# openSX70_MEROE_V7-5_20190606-TSL237T.net
KiCad netlist of a schematic drawn in EAGLE
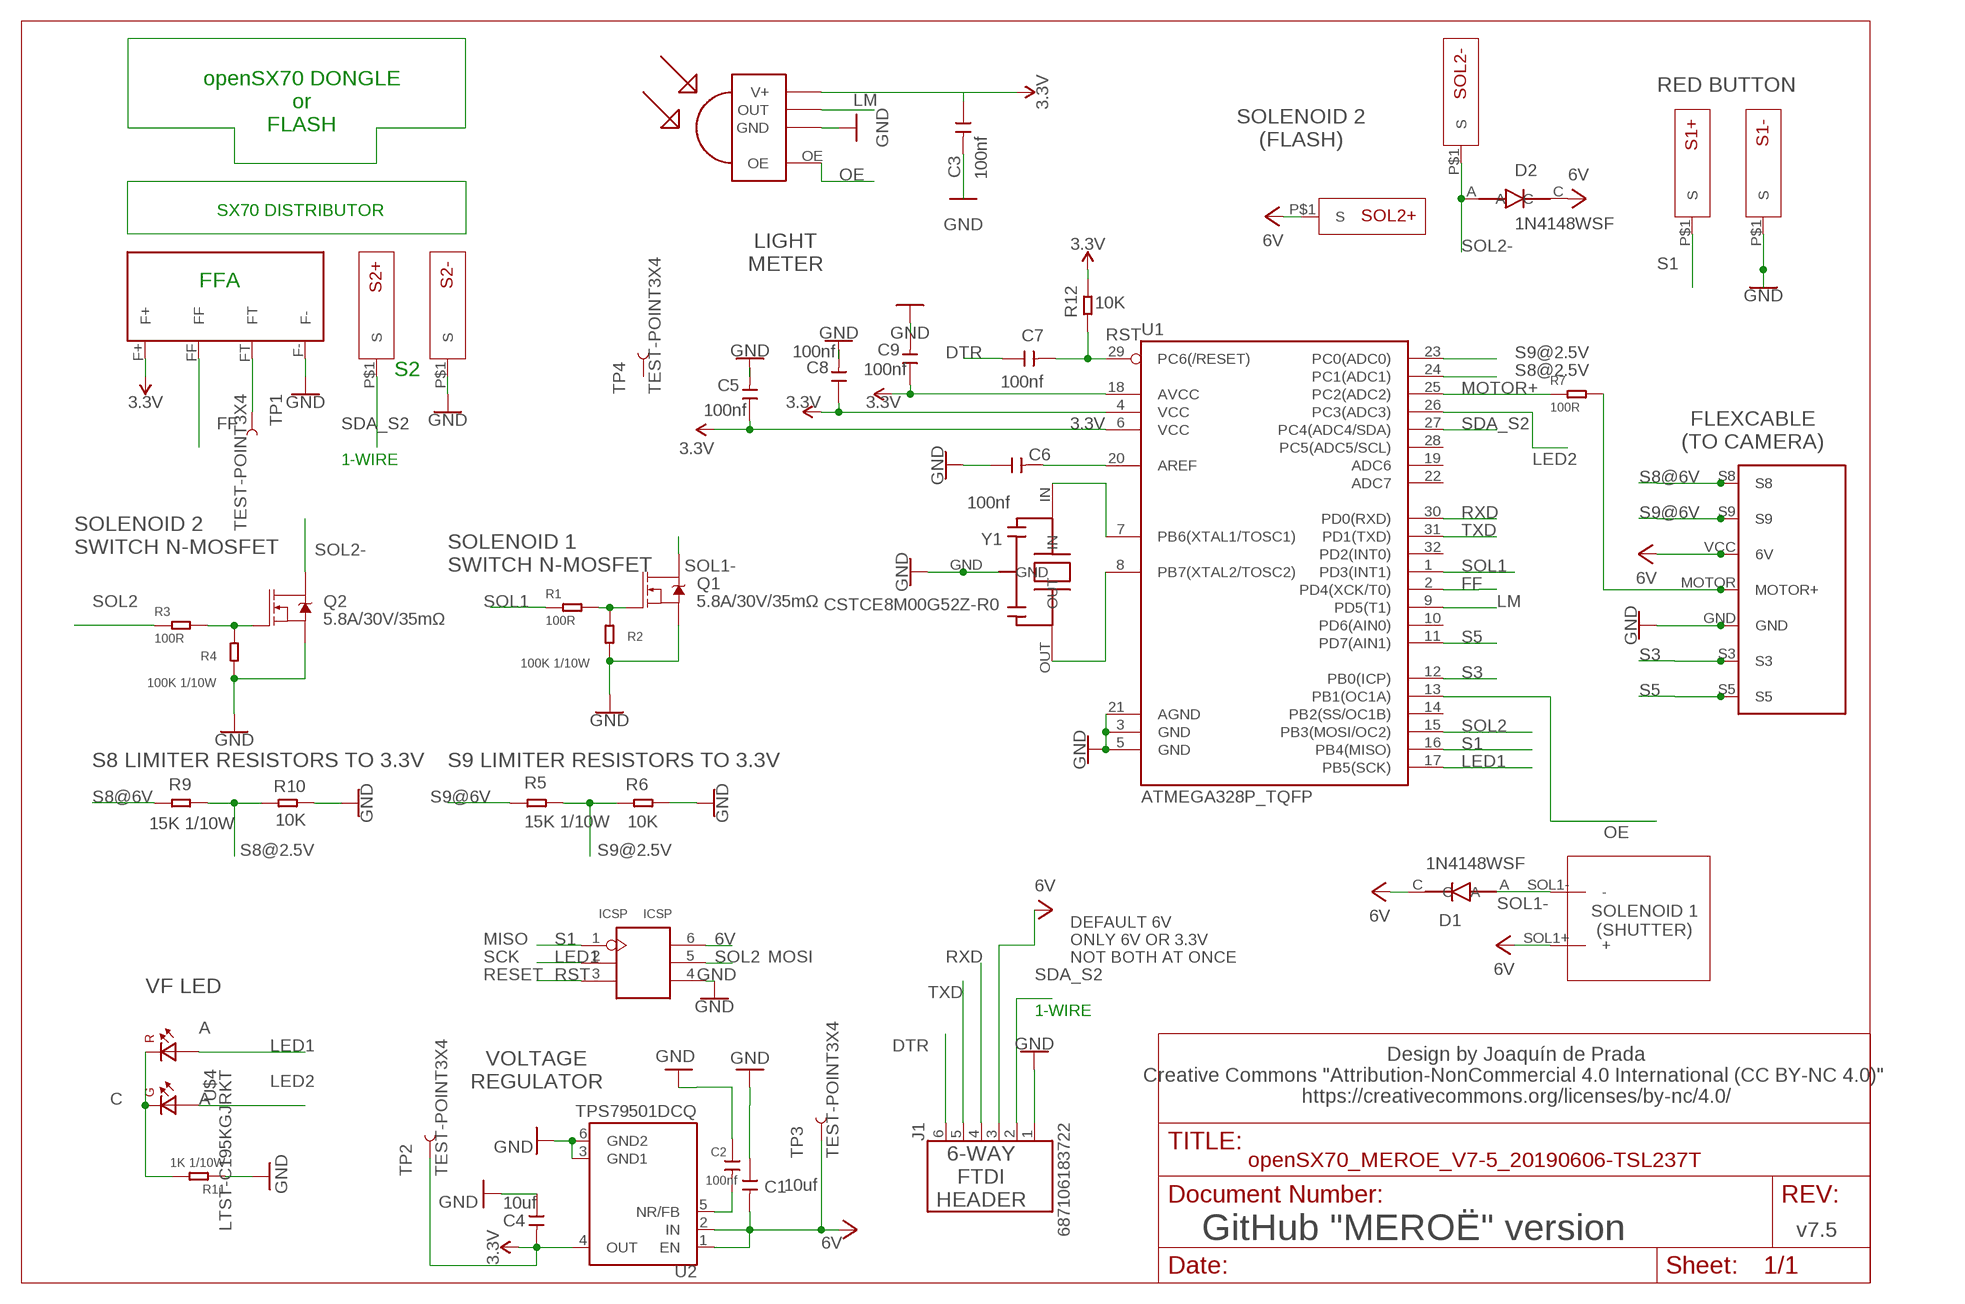
[diagram p0: schematic, sheet 1]

(export (version "E")
  (design (tool "Eeschema 10.0.6"))
  (components
    (comp (ref "C1")
      (value "10uf")
      (footprint "eagle-import:C0603")
      (fields (field (name "MPN") "CC0603KRX5R6BB106"))
      (libsource (lib "eagle-import") (part "CERAMIC-10UF-10V-10%-X5R(0603)"))
    )
    (comp (ref "C2")
      (value "100nf")
      (footprint "eagle-import:C0603")
      (fields (field (name "MPN") "CC0603KRX7R9BB104"))
      (libsource (lib "eagle-import") (part "CERAMIC-100NF-50V-10%-X7R(0603)"))
    )
    (comp (ref "C3")
      (value "100nf")
      (footprint "eagle-import:C0603")
      (fields (field (name "MPN") "CC0603KRX7R9BB104"))
      (libsource (lib "eagle-import") (part "CERAMIC-100NF-50V-10%-X7R(0603)"))
    )
    (comp (ref "C4")
      (value "10uf")
      (footprint "eagle-import:C0603")
      (fields (field (name "MPN") "CC0603KRX5R6BB106"))
      (libsource (lib "eagle-import") (part "CERAMIC-10UF-10V-10%-X5R(0603)"))
    )
    (comp (ref "C5")
      (value "100nf")
      (footprint "eagle-import:C0603")
      (fields (field (name "MPN") "CC0603KRX7R9BB104"))
      (libsource (lib "eagle-import") (part "CERAMIC-100NF-50V-10%-X7R(0603)"))
    )
    (comp (ref "C6")
      (value "100nf")
      (footprint "eagle-import:C0603")
      (fields (field (name "MPN") "CC0603KRX7R9BB104"))
      (libsource (lib "eagle-import") (part "CERAMIC-100NF-50V-10%-X7R(0603)"))
    )
    (comp (ref "C7")
      (value "100nf")
      (footprint "eagle-import:C0603")
      (fields (field (name "MPN") "CC0603KRX7R9BB104"))
      (libsource (lib "eagle-import") (part "CERAMIC-100NF-50V-10%-X7R(0603)"))
    )
    (comp (ref "C8")
      (value "100nf")
      (footprint "eagle-import:C0603")
      (fields (field (name "MPN") "CC0603KRX7R9BB104"))
      (libsource (lib "eagle-import") (part "CERAMIC-100NF-50V-10%-X7R(0603)"))
    )
    (comp (ref "C9")
      (value "100nf")
      (footprint "eagle-import:C0603")
      (fields (field (name "MPN") "CC0603KRX7R9BB104"))
      (libsource (lib "eagle-import") (part "CERAMIC-100NF-50V-10%-X7R(0603)"))
    )
    (comp (ref "D1")
      (value "1N4148WSF")
      (footprint "eagle-import:SODFL2512X100N")
      (fields (field (name "MANUFACTURER") "Fairchild Semiconductor"))
      (libsource (lib "eagle-import") (part "1N4148WS"))
    )
    (comp (ref "D2")
      (value "1N4148WSF")
      (footprint "eagle-import:SODFL2512X100N")
      (fields (field (name "MANUFACTURER") "Fairchild Semiconductor"))
      (libsource (lib "eagle-import") (part "1N4148WS"))
    )
    (comp (ref "ICSP")
      (value "ICSP")
      (footprint "eagle-import:H2X3-2.54")
      (libsource (lib "eagle-import") (part "ICSP"))
    )
    (comp (ref "J1")
      (value "687106183722")
      (footprint "eagle-import:687106183722")
      (fields (field (name "MF") "Wurth Electronics"))
      (libsource (lib "eagle-import") (part "687106183722"))
    )
    (comp (ref "Q1")
      (value "5.8A/30V/35mΩ")
      (footprint "eagle-import:SOT23-3")
      (libsource (lib "eagle-import") (part "MOSFET-NCH-AO3404A"))
    )
    (comp (ref "Q2")
      (value "5.8A/30V/35mΩ")
      (footprint "eagle-import:SOT23-3")
      (libsource (lib "eagle-import") (part "MOSFET-NCH-AO3404A"))
    )
    (comp (ref "R1")
      (value "100R")
      (footprint "eagle-import:R0603")
      (fields (field (name "MPN") "RC0603JR-07100RL"))
      (libsource (lib "eagle-import") (part "SMD-RES-100R-5%-1/10W(0603)"))
    )
    (comp (ref "R2")
      (value "100K 1/10W")
      (footprint "eagle-import:R0603")
      (fields (field (name "MPN") "RC0603JR-07100KL"))
      (libsource (lib "eagle-import") (part "SMD-RES-100K-5%-1/10W(0603)"))
    )
    (comp (ref "R3")
      (value "100R")
      (footprint "eagle-import:R0603")
      (fields (field (name "MPN") "RC0603JR-07100RL"))
      (libsource (lib "eagle-import") (part "SMD-RES-100R-5%-1/10W(0603)"))
    )
    (comp (ref "R4")
      (value "100K 1/10W")
      (footprint "eagle-import:R0603")
      (fields (field (name "MPN") "RC0603JR-07100KL"))
      (libsource (lib "eagle-import") (part "SMD-RES-100K-5%-1/10W(0603)"))
    )
    (comp (ref "R5")
      (value "15K 1/10W")
      (footprint "eagle-import:R0603")
      (fields (field (name "MPN") "RC0603FR-0715KL"))
      (libsource (lib "eagle-import") (part "SMD-RES-15K-1%-1/10W(0603)"))
    )
    (comp (ref "R6")
      (value "10K")
      (footprint "eagle-import:R0603")
      (fields (field (name "MPN") "RC0603FR-0710KL"))
      (libsource (lib "eagle-import") (part "SMD-RES-10K-1%-1/10W(0603)"))
    )
    (comp (ref "R7")
      (value "100R")
      (footprint "eagle-import:R0603")
      (fields (field (name "MPN") "RC0603JR-07100RL"))
      (libsource (lib "eagle-import") (part "SMD-RES-100R-5%-1/10W(0603)"))
    )
    (comp (ref "R9")
      (value "15K 1/10W")
      (footprint "eagle-import:R0603")
      (fields (field (name "MPN") "RC0603FR-0715KL"))
      (libsource (lib "eagle-import") (part "SMD-RES-15K-1%-1/10W(0603)"))
    )
    (comp (ref "R10")
      (value "10K")
      (footprint "eagle-import:R0603")
      (fields (field (name "MPN") "RC0603FR-0710KL"))
      (libsource (lib "eagle-import") (part "SMD-RES-10K-1%-1/10W(0603)"))
    )
    (comp (ref "R11")
      (value "1K 1/10W")
      (footprint "eagle-import:R0603")
      (fields (field (name "MPN") "RC0603JR-071KL"))
      (libsource (lib "eagle-import") (part "SMD-RES-1K-5%-1/10W(0603)"))
    )
    (comp (ref "R12")
      (value "10K")
      (footprint "eagle-import:R0603")
      (fields (field (name "MPN") "RC0603FR-0710KL"))
      (libsource (lib "eagle-import") (part "SMD-RES-10K-1%-1/10W(0603)"))
    )
    (comp (ref "S1+")
      (value "SX70-S-PAD-NEW")
      (footprint "eagle-import:SX70-S-PAD2")
      (libsource (lib "eagle-import") (part "SX70-S-PAD-NEW"))
    )
    (comp (ref "S1-")
      (value "SX70-S-PAD-NEW")
      (footprint "eagle-import:SX70-S-PAD2")
      (libsource (lib "eagle-import") (part "SX70-S-PAD-NEW"))
    )
    (comp (ref "S2+")
      (value "SX70-S-PAD-NEW")
      (footprint "eagle-import:SX70-S-PAD2")
      (libsource (lib "eagle-import") (part "SX70-S-PAD-NEW"))
    )
    (comp (ref "S2-")
      (value "SX70-S-PAD-NEW")
      (footprint "eagle-import:SX70-S-PAD2")
      (libsource (lib "eagle-import") (part "SX70-S-PAD-NEW"))
    )
    (comp (ref "SOL1")
      (value "SX70-SOLENOID1-2PADS")
      (footprint "eagle-import:SX70-SOLENOID1-2")
      (libsource (lib "eagle-import") (part "SX70-SOLENOID1-2PADS"))
    )
    (comp (ref "SOL2+")
      (value "SX70-S-PAD-NEW")
      (footprint "eagle-import:SX70-S-PAD2")
      (libsource (lib "eagle-import") (part "SX70-S-PAD-NEW"))
    )
    (comp (ref "SOL2-")
      (value "SX70-S-PAD-NEW")
      (footprint "eagle-import:SX70-S-PAD2")
      (libsource (lib "eagle-import") (part "SX70-S-PAD-NEW"))
    )
    (comp (ref "TP1")
      (value "TEST-POINT3X4")
      (footprint "eagle-import:PAD.03X.04")
      (libsource (lib "eagle-import") (part "TEST-POINT3X4"))
    )
    (comp (ref "TP2")
      (value "TEST-POINT3X4")
      (footprint "eagle-import:PAD.03X.04")
      (libsource (lib "eagle-import") (part "TEST-POINT3X4"))
    )
    (comp (ref "TP3")
      (value "TEST-POINT3X4")
      (footprint "eagle-import:PAD.03X.04")
      (libsource (lib "eagle-import") (part "TEST-POINT3X4"))
    )
    (comp (ref "TP4")
      (value "TEST-POINT3X4")
      (footprint "eagle-import:PAD.03X.04")
      (libsource (lib "eagle-import") (part "TEST-POINT3X4"))
    )
    (comp (ref "U$1")
      (value "SX70-7-PAD")
      (footprint "eagle-import:SX70-7-PAD-PROPER")
      (libsource (lib "eagle-import") (part "SX70-7-PAD"))
    )
    (comp (ref "U$2")
      (value "FFA")
      (footprint "eagle-import:FFA-PAD-PACKAGE")
      (libsource (lib "eagle-import") (part "SX70-FFA-PAD"))
    )
    (comp (ref "U$3")
      (value "TSL237T")
      (footprint "eagle-import:TSL237T")
      (libsource (lib "eagle-import") (part "TSL237T"))
    )
    (comp (ref "U$4")
      (value "LTST-C195KGJRKT")
      (footprint "eagle-import:LTST-BILED-15X16")
      (fields (field (name "MF") "Lite-On Inc."))
      (libsource (lib "eagle-import") (part "LTST-C195KGJRKT"))
    )
    (comp (ref "U1")
      (value "ATMEGA328P_TQFP")
      (footprint "eagle-import:TQFP32-08")
      (libsource (lib "eagle-import") (part "ATMEGA328P_TQFP"))
    )
    (comp (ref "U2")
      (value "TPS79501DCQ")
      (footprint "eagle-import:SOT127P706X180-6N")
      (fields (field (name "DIGI-KEY_PART_NUMBER") "296-27102-5-ND") (field (name "MF") "Texas Instruments"))
      (libsource (lib "eagle-import") (part "TPS79501DCQ"))
    )
    (comp (ref "Y1")
      (value "CSTCE8M00G52Z-R0")
      (footprint "eagle-import:CFP95P160X100-3N")
      (fields (field (name "MF") "Murata") (field (name "MP") "CSTCE16M0V53-R0"))
      (libsource (lib "eagle-import") (part "CSTCE16M0V53-R0"))
    )
  )
  (nets
    (net (code "1") (name "/DTR") (class "Default")
      (node (ref "C7") (pin "1") (pinfunction "1_1") (pintype "passive"))
      (node (ref "J1") (pin "6") (pinfunction "1_6") (pintype "passive"))
    )
    (net (code "2") (name "/FF") (class "Default")
      (node (ref "U$2") (pin "FF") (pinfunction "FF_FF") (pintype "bidirectional"))
      (node (ref "U1") (pin "2") (pinfunction "PD4(XCK/T0)_2") (pintype "bidirectional"))
    )
    (net (code "3") (name "/LED1") (class "Default")
      (node (ref "ICSP") (pin "2") (pinfunction "SCK_2") (pintype "bidirectional"))
      (node (ref "U$4") (pin "P$2") (pinfunction "A2_P$2") (pintype "passive"))
      (node (ref "U1") (pin "17") (pinfunction "PB5(SCK)_17") (pintype "bidirectional"))
    )
    (net (code "4") (name "/LED2") (class "Default")
      (node (ref "U$4") (pin "P$1") (pinfunction "A1_P$1") (pintype "passive"))
      (node (ref "U1") (pin "26") (pinfunction "PC3(ADC3)_26") (pintype "bidirectional"))
    )
    (net (code "5") (name "/LM") (class "Default")
      (node (ref "U$3") (pin "OUT") (pinfunction "OUT_OUT") (pintype "bidirectional"))
      (node (ref "U1") (pin "9") (pinfunction "PD5(T1)_9") (pintype "bidirectional"))
    )
    (net (code "6") (name "/MOTOR+") (class "Default")
      (node (ref "R7") (pin "1") (pinfunction "1_1") (pintype "passive"))
      (node (ref "U1") (pin "25") (pinfunction "PC2(ADC2)_25") (pintype "bidirectional"))
    )
    (net (code "7") (name "/OE") (class "Default")
      (node (ref "U$3") (pin "OE") (pinfunction "OE_OE") (pintype "bidirectional"))
      (node (ref "U1") (pin "13") (pinfunction "PB1(OC1A)_13") (pintype "bidirectional"))
    )
    (net (code "8") (name "/RST") (class "Default")
      (node (ref "C7") (pin "2") (pinfunction "2_2") (pintype "passive"))
      (node (ref "ICSP") (pin "3") (pinfunction "RST_3") (pintype "bidirectional"))
      (node (ref "R12") (pin "1") (pinfunction "1_1") (pintype "passive"))
      (node (ref "U1") (pin "29") (pinfunction "PC6(/RESET)_29") (pintype "bidirectional"))
    )
    (net (code "9") (name "/RXD") (class "Default")
      (node (ref "J1") (pin "4") (pinfunction "3_4") (pintype "passive"))
      (node (ref "U1") (pin "30") (pinfunction "PD0(RXD)_30") (pintype "bidirectional"))
    )
    (net (code "10") (name "/S1") (class "Default")
      (node (ref "ICSP") (pin "1") (pinfunction "MISO_1") (pintype "bidirectional"))
      (node (ref "S1+") (pin "P$1") (pinfunction "S_P$1") (pintype "bidirectional"))
      (node (ref "U1") (pin "16") (pinfunction "PB4(MISO)_16") (pintype "bidirectional"))
    )
    (net (code "11") (name "/S3") (class "Default")
      (node (ref "U$1") (pin "S3") (pinfunction "S3_S3") (pintype "bidirectional"))
      (node (ref "U1") (pin "12") (pinfunction "PB0(ICP)_12") (pintype "bidirectional"))
    )
    (net (code "12") (name "/S5") (class "Default")
      (node (ref "U$1") (pin "S5") (pinfunction "S5_S5") (pintype "bidirectional"))
      (node (ref "U1") (pin "11") (pinfunction "PD7(AIN1)_11") (pintype "bidirectional"))
    )
    (net (code "13") (name "/S8@2.5V") (class "Default")
      (node (ref "R10") (pin "1") (pinfunction "1_1") (pintype "passive"))
      (node (ref "R9") (pin "2") (pinfunction "2_2") (pintype "passive"))
      (node (ref "U1") (pin "24") (pinfunction "PC1(ADC1)_24") (pintype "bidirectional"))
    )
    (net (code "14") (name "/S8@6V") (class "Default")
      (node (ref "R9") (pin "1") (pinfunction "1_1") (pintype "passive"))
      (node (ref "U$1") (pin "S8") (pinfunction "S8_S8") (pintype "bidirectional"))
    )
    (net (code "15") (name "/S9@2.5V") (class "Default")
      (node (ref "R5") (pin "2") (pinfunction "2_2") (pintype "passive"))
      (node (ref "R6") (pin "1") (pinfunction "1_1") (pintype "passive"))
      (node (ref "U1") (pin "23") (pinfunction "PC0(ADC0)_23") (pintype "bidirectional"))
    )
    (net (code "16") (name "/S9@6V") (class "Default")
      (node (ref "R5") (pin "1") (pinfunction "1_1") (pintype "passive"))
      (node (ref "U$1") (pin "S9") (pinfunction "S9_S9") (pintype "bidirectional"))
    )
    (net (code "17") (name "/SDA_S2") (class "Default")
      (node (ref "J1") (pin "2") (pinfunction "5_2") (pintype "passive"))
      (node (ref "S2+") (pin "P$1") (pinfunction "S_P$1") (pintype "bidirectional"))
      (node (ref "U1") (pin "27") (pinfunction "PC4(ADC4/SDA)_27") (pintype "bidirectional"))
    )
    (net (code "18") (name "/SOL1") (class "Default")
      (node (ref "R1") (pin "1") (pinfunction "1_1") (pintype "passive"))
      (node (ref "U1") (pin "1") (pinfunction "PD3(INT1)_1") (pintype "bidirectional"))
    )
    (net (code "19") (name "/SOL1-") (class "Default")
      (node (ref "D1") (pin "A") (pinfunction "A_A") (pintype "passive"))
      (node (ref "Q1") (pin "3") (pinfunction "D_3") (pintype "bidirectional"))
      (node (ref "SOL1") (pin "SOL1-") (pinfunction "-_SOL1-") (pintype "bidirectional"))
    )
    (net (code "20") (name "/SOL2") (class "Default")
      (node (ref "ICSP") (pin "5") (pinfunction "MOSI_5") (pintype "bidirectional"))
      (node (ref "R3") (pin "1") (pinfunction "1_1") (pintype "passive"))
      (node (ref "U1") (pin "15") (pinfunction "PB3(MOSI/OC2)_15") (pintype "bidirectional"))
    )
    (net (code "21") (name "/SOL2-") (class "Default")
      (node (ref "D2") (pin "A") (pinfunction "A_A") (pintype "passive"))
      (node (ref "Q2") (pin "3") (pinfunction "D_3") (pintype "bidirectional"))
      (node (ref "SOL2-") (pin "P$1") (pinfunction "S_P$1") (pintype "bidirectional"))
    )
    (net (code "22") (name "/TXD") (class "Default")
      (node (ref "J1") (pin "5") (pinfunction "2_5") (pintype "passive"))
      (node (ref "U1") (pin "31") (pinfunction "PD1(TXD)_31") (pintype "bidirectional"))
    )
    (net (code "23") (name "3.3V") (class "Default")
      (node (ref "C3") (pin "1") (pinfunction "1_1") (pintype "passive"))
      (node (ref "C4") (pin "2") (pinfunction "2_2") (pintype "passive"))
      (node (ref "C5") (pin "1") (pinfunction "1_1") (pintype "passive"))
      (node (ref "C8") (pin "1") (pinfunction "1_1") (pintype "passive"))
      (node (ref "C9") (pin "1") (pinfunction "1_1") (pintype "passive"))
      (node (ref "R12") (pin "2") (pinfunction "2_2") (pintype "passive"))
      (node (ref "TP2") (pin "P$1") (pinfunction "1_P$1") (pintype "bidirectional"))
      (node (ref "U$2") (pin "F+") (pinfunction "F+_F+") (pintype "bidirectional"))
      (node (ref "U$3") (pin "VDD") (pinfunction "V+_VDD") (pintype "bidirectional"))
      (node (ref "U1") (pin "18") (pinfunction "AVCC_18") (pintype "bidirectional"))
      (node (ref "U1") (pin "4") (pinfunction "VCC_4") (pintype "bidirectional"))
      (node (ref "U1") (pin "6") (pinfunction "VCC_6") (pintype "bidirectional"))
      (node (ref "U2") (pin "4") (pinfunction "OUT_4") (pintype "output"))
    )
    (net (code "24") (name "6V") (class "Default")
      (node (ref "C1") (pin "2") (pinfunction "2_2") (pintype "passive"))
      (node (ref "D1") (pin "C") (pinfunction "C_C") (pintype "passive"))
      (node (ref "D2") (pin "C") (pinfunction "C_C") (pintype "passive"))
      (node (ref "ICSP") (pin "6") (pinfunction "VCC_6") (pintype "bidirectional"))
      (node (ref "J1") (pin "3") (pinfunction "4_3") (pintype "passive"))
      (node (ref "SOL1") (pin "SOL1+") (pinfunction "+_SOL1+") (pintype "bidirectional"))
      (node (ref "SOL2+") (pin "P$1") (pinfunction "S_P$1") (pintype "bidirectional"))
      (node (ref "TP3") (pin "P$1") (pinfunction "1_P$1") (pintype "bidirectional"))
      (node (ref "U$1") (pin "VCC") (pinfunction "6V_VCC") (pintype "bidirectional"))
      (node (ref "U2") (pin "1") (pinfunction "EN_1") (pintype "input"))
      (node (ref "U2") (pin "2") (pinfunction "IN_2") (pintype "input"))
    )
    (net (code "25") (name "GND") (class "Default")
      (node (ref "C1") (pin "1") (pinfunction "1_1") (pintype "passive"))
      (node (ref "C2") (pin "1") (pinfunction "1_1") (pintype "passive"))
      (node (ref "C3") (pin "2") (pinfunction "2_2") (pintype "passive"))
      (node (ref "C4") (pin "1") (pinfunction "1_1") (pintype "passive"))
      (node (ref "C5") (pin "2") (pinfunction "2_2") (pintype "passive"))
      (node (ref "C6") (pin "1") (pinfunction "1_1") (pintype "passive"))
      (node (ref "C8") (pin "2") (pinfunction "2_2") (pintype "passive"))
      (node (ref "C9") (pin "2") (pinfunction "2_2") (pintype "passive"))
      (node (ref "ICSP") (pin "4") (pinfunction "GND_4") (pintype "bidirectional"))
      (node (ref "J1") (pin "1") (pinfunction "6_1") (pintype "passive"))
      (node (ref "Q1") (pin "2") (pinfunction "S_2") (pintype "bidirectional"))
      (node (ref "Q2") (pin "2") (pinfunction "S_2") (pintype "bidirectional"))
      (node (ref "R10") (pin "2") (pinfunction "2_2") (pintype "passive"))
      (node (ref "R11") (pin "1") (pinfunction "1_1") (pintype "passive"))
      (node (ref "R2") (pin "1") (pinfunction "1_1") (pintype "passive"))
      (node (ref "R4") (pin "1") (pinfunction "1_1") (pintype "passive"))
      (node (ref "R6") (pin "2") (pinfunction "2_2") (pintype "passive"))
      (node (ref "S1-") (pin "P$1") (pinfunction "S_P$1") (pintype "bidirectional"))
      (node (ref "S2-") (pin "P$1") (pinfunction "S_P$1") (pintype "bidirectional"))
      (node (ref "U$1") (pin "GND") (pinfunction "GND_GND") (pintype "bidirectional"))
      (node (ref "U$2") (pin "F-") (pinfunction "F-_F-") (pintype "bidirectional"))
      (node (ref "U$3") (pin "GND") (pinfunction "GND_GND") (pintype "bidirectional"))
      (node (ref "U1") (pin "21") (pinfunction "AGND_21") (pintype "bidirectional"))
      (node (ref "U1") (pin "3") (pinfunction "GND_3") (pintype "bidirectional"))
      (node (ref "U1") (pin "5") (pinfunction "GND_5") (pintype "bidirectional"))
      (node (ref "U2") (pin "3") (pinfunction "GND1_3") (pintype "power_in"))
      (node (ref "U2") (pin "6") (pinfunction "GND2_6") (pintype "power_in"))
      (node (ref "Y1") (pin "GND") (pinfunction "GND_GND") (pintype "passive"))
    )
    (net (code "26") (name "Net-(Q1-G)") (class "Default")
      (node (ref "Q1") (pin "1") (pinfunction "G_1") (pintype "bidirectional"))
      (node (ref "R1") (pin "2") (pinfunction "2_2") (pintype "passive"))
      (node (ref "R2") (pin "2") (pinfunction "2_2") (pintype "passive"))
    )
    (net (code "27") (name "Net-(Q2-G)") (class "Default")
      (node (ref "Q2") (pin "1") (pinfunction "G_1") (pintype "bidirectional"))
      (node (ref "R3") (pin "2") (pinfunction "2_2") (pintype "passive"))
      (node (ref "R4") (pin "2") (pinfunction "2_2") (pintype "passive"))
    )
    (net (code "28") (name "Net-(TP1-1)") (class "Default")
      (node (ref "TP1") (pin "P$1") (pinfunction "1_P$1") (pintype "bidirectional"))
      (node (ref "U$2") (pin "FT") (pinfunction "FT_FT") (pintype "bidirectional"))
    )
    (net (code "29") (name "Net-(U$1-MOTOR+)") (class "Default")
      (node (ref "R7") (pin "2") (pinfunction "2_2") (pintype "passive"))
      (node (ref "U$1") (pin "MOTOR") (pinfunction "MOTOR+_MOTOR") (pintype "bidirectional"))
    )
    (net (code "30") (name "Net-(U$4-K1)") (class "Default")
      (node (ref "R11") (pin "2") (pinfunction "2_2") (pintype "passive"))
      (node (ref "U$4") (pin "P$3") (pinfunction "K1_P$3") (pintype "passive"))
      (node (ref "U$4") (pin "P$4") (pinfunction "K2_P$4") (pintype "passive"))
    )
    (net (code "31") (name "Net-(U1-AREF)") (class "Default")
      (node (ref "C6") (pin "2") (pinfunction "2_2") (pintype "passive"))
      (node (ref "U1") (pin "20") (pinfunction "AREF_20") (pintype "bidirectional"))
    )
    (net (code "32") (name "Net-(U1-PB6(XTAL1{slash}TOSC1))") (class "Default")
      (node (ref "U1") (pin "7") (pinfunction "PB6(XTAL1/TOSC1)_7") (pintype "bidirectional"))
      (node (ref "Y1") (pin "IN") (pinfunction "IN_IN") (pintype "input"))
    )
    (net (code "33") (name "Net-(U1-PB7(XTAL2{slash}TOSC2))") (class "Default")
      (node (ref "U1") (pin "8") (pinfunction "PB7(XTAL2/TOSC2)_8") (pintype "bidirectional"))
      (node (ref "Y1") (pin "OUT") (pinfunction "OUT_OUT") (pintype "output"))
    )
    (net (code "34") (name "Net-(U2-NR{slash}FB)") (class "Default")
      (node (ref "C2") (pin "2") (pinfunction "2_2") (pintype "passive"))
      (node (ref "U2") (pin "5") (pinfunction "NR/FB_5") (pintype "input"))
    )
    (net (code "35") (name "unconnected-(TP4-1-PadP$1)") (class "Default")
      (node (ref "TP4") (pin "P$1") (pinfunction "1_P$1") (pintype "bidirectional"))
    )
    (net (code "36") (name "unconnected-(U1-ADC6-Pad19)") (class "Default")
      (node (ref "U1") (pin "19") (pinfunction "ADC6_19") (pintype "bidirectional"))
    )
    (net (code "37") (name "unconnected-(U1-ADC7-Pad22)") (class "Default")
      (node (ref "U1") (pin "22") (pinfunction "ADC7_22") (pintype "bidirectional"))
    )
    (net (code "38") (name "unconnected-(U1-PB2(SS{slash}OC1B)-Pad14)") (class "Default")
      (node (ref "U1") (pin "14") (pinfunction "PB2(SS/OC1B)_14") (pintype "bidirectional"))
    )
    (net (code "39") (name "unconnected-(U1-PC5(ADC5{slash}SCL)-Pad28)") (class "Default")
      (node (ref "U1") (pin "28") (pinfunction "PC5(ADC5/SCL)_28") (pintype "bidirectional"))
    )
    (net (code "40") (name "unconnected-(U1-PD2(INT0)-Pad32)") (class "Default")
      (node (ref "U1") (pin "32") (pinfunction "PD2(INT0)_32") (pintype "bidirectional"))
    )
    (net (code "41") (name "unconnected-(U1-PD6(AIN0)-Pad10)") (class "Default")
      (node (ref "U1") (pin "10") (pinfunction "PD6(AIN0)_10") (pintype "bidirectional"))
    )
  )
)
